# Button_Board_RevA.net
KiCad netlist of a schematic drawn in EAGLE
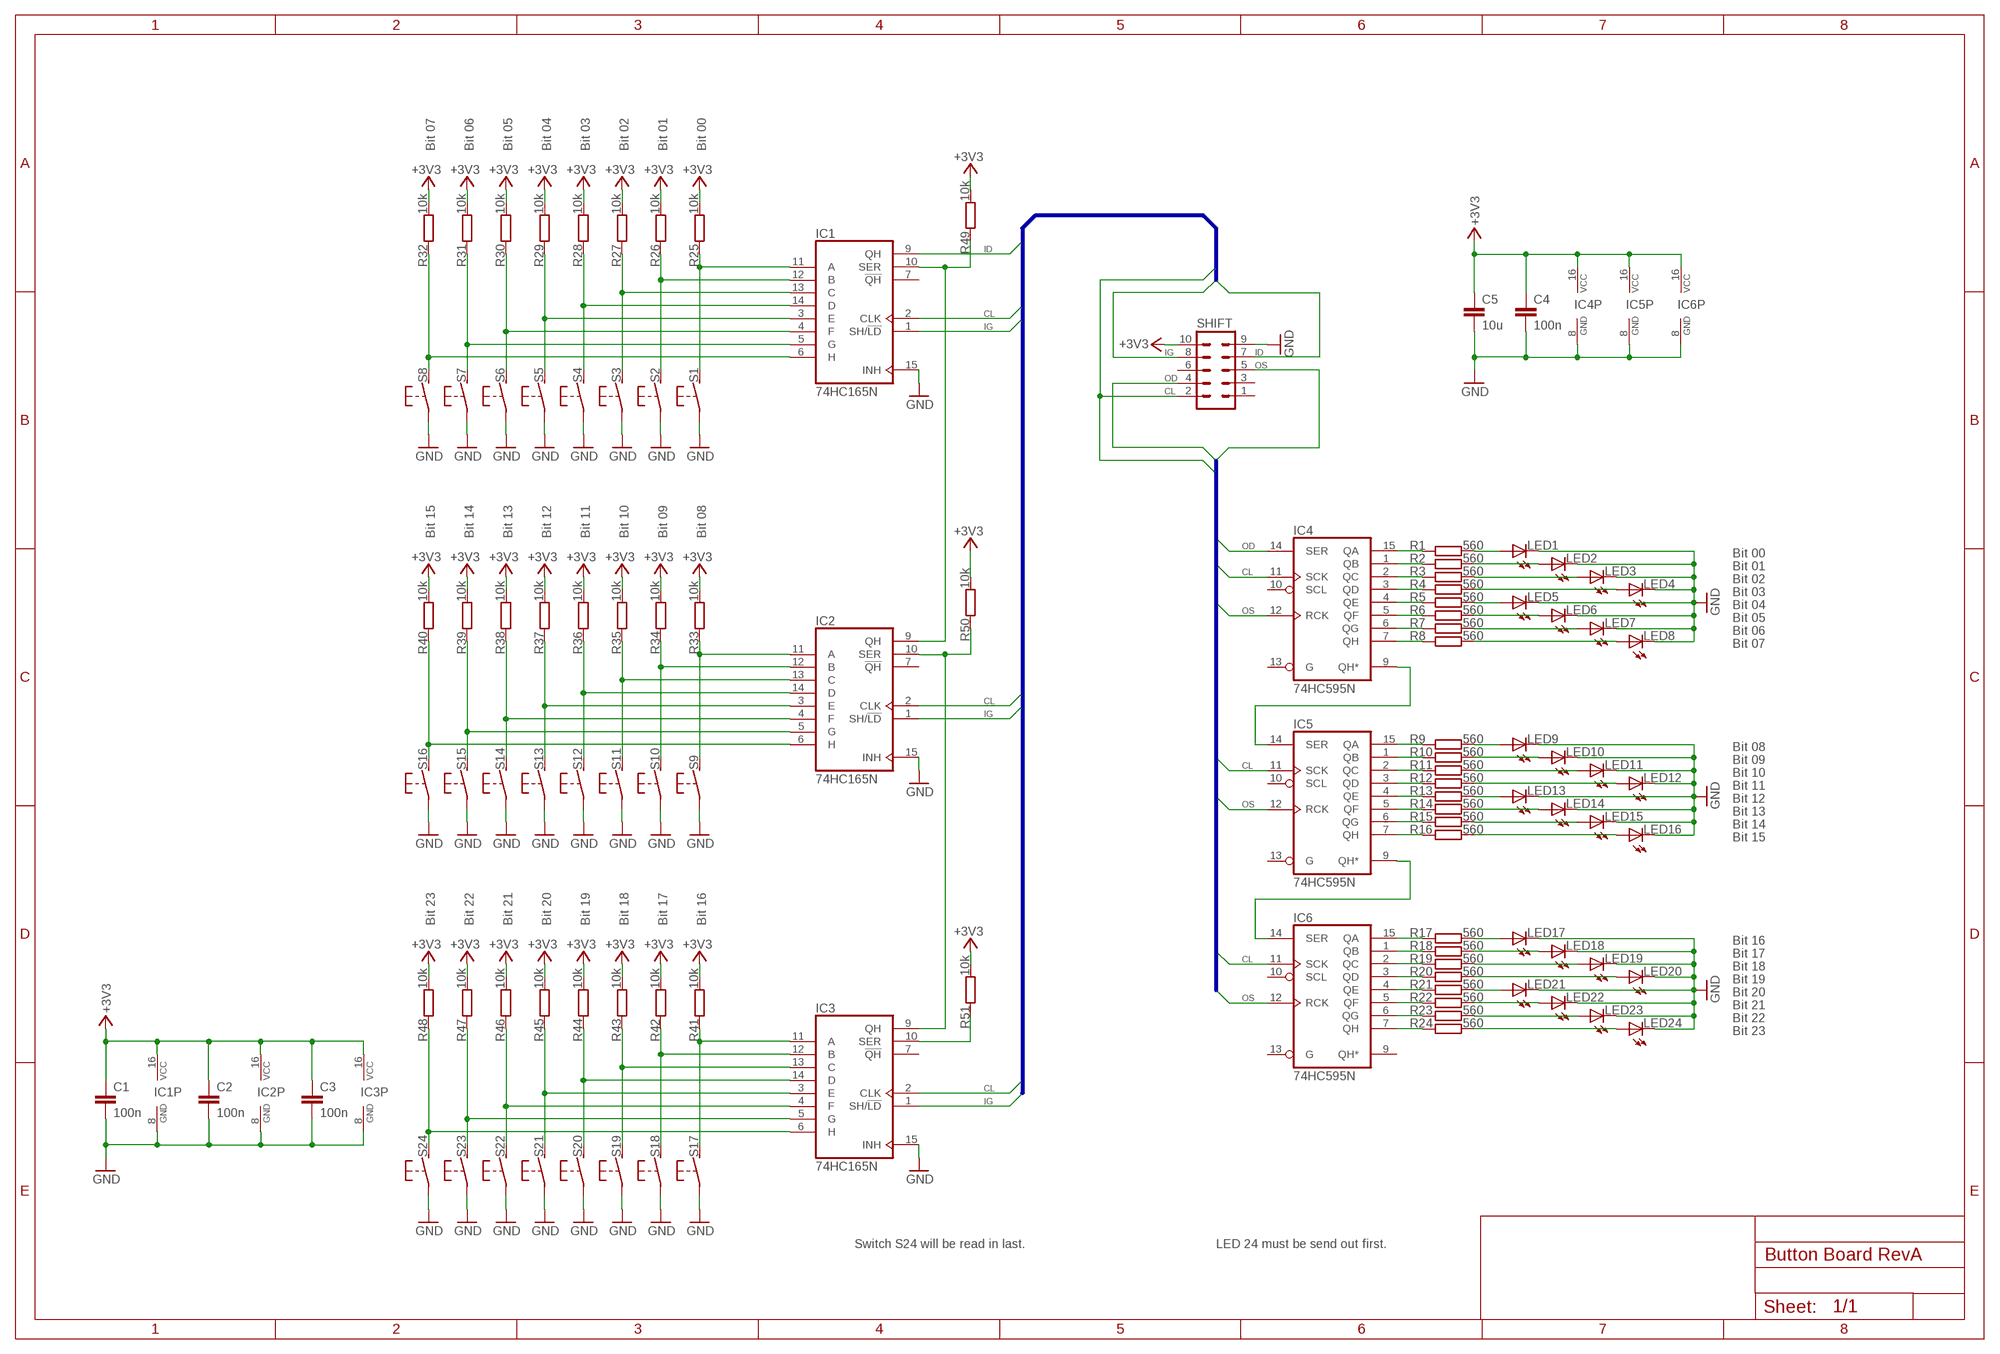
[diagram p0: schematic, sheet 1]

(export (version "E")
  (design (tool "Eeschema 10.0.6"))
  (components
    (comp (ref "C1")
      (value "100n")
      (footprint "eagle-import:C025-025X050")
      (libsource (lib "eagle-import") (part "C-EU025-025X050"))
    )
    (comp (ref "C2")
      (value "100n")
      (footprint "eagle-import:C025-025X050")
      (libsource (lib "eagle-import") (part "C-EU025-025X050"))
    )
    (comp (ref "C3")
      (value "100n")
      (footprint "eagle-import:C025-025X050")
      (libsource (lib "eagle-import") (part "C-EU025-025X050"))
    )
    (comp (ref "C4")
      (value "100n")
      (footprint "eagle-import:C025-025X050")
      (libsource (lib "eagle-import") (part "C-EU025-025X050"))
    )
    (comp (ref "C5")
      (value "10u")
      (footprint "eagle-import:C025-025X050")
      (libsource (lib "eagle-import") (part "C-EU025-025X050"))
    )
    (comp (ref "IC1")
      (value "74HC165N")
      (footprint "eagle-import:DIL16")
      (libsource (lib "eagle-import") (part "74165NHC"))
    )
    (comp (ref "IC2")
      (value "74HC165N")
      (footprint "eagle-import:DIL16")
      (libsource (lib "eagle-import") (part "74165NHC"))
    )
    (comp (ref "IC3")
      (value "74HC165N")
      (footprint "eagle-import:DIL16")
      (libsource (lib "eagle-import") (part "74165NHC"))
    )
    (comp (ref "IC4")
      (value "74HC595N")
      (footprint "eagle-import:DIL16")
      (libsource (lib "eagle-import") (part "74595NHC"))
    )
    (comp (ref "IC5")
      (value "74HC595N")
      (footprint "eagle-import:DIL16")
      (libsource (lib "eagle-import") (part "74595NHC"))
    )
    (comp (ref "IC6")
      (value "74HC595N")
      (footprint "eagle-import:DIL16")
      (libsource (lib "eagle-import") (part "74595NHC"))
    )
    (comp (ref "LED1")
      (value "LED3MM")
      (footprint "eagle-import:LED3MM")
      (libsource (lib "eagle-import") (part "LED3MM"))
    )
    (comp (ref "LED2")
      (value "LED3MM")
      (footprint "eagle-import:LED3MM")
      (libsource (lib "eagle-import") (part "LED3MM"))
    )
    (comp (ref "LED3")
      (value "LED3MM")
      (footprint "eagle-import:LED3MM")
      (libsource (lib "eagle-import") (part "LED3MM"))
    )
    (comp (ref "LED4")
      (value "LED3MM")
      (footprint "eagle-import:LED3MM")
      (libsource (lib "eagle-import") (part "LED3MM"))
    )
    (comp (ref "LED5")
      (value "LED3MM")
      (footprint "eagle-import:LED3MM")
      (libsource (lib "eagle-import") (part "LED3MM"))
    )
    (comp (ref "LED6")
      (value "LED3MM")
      (footprint "eagle-import:LED3MM")
      (libsource (lib "eagle-import") (part "LED3MM"))
    )
    (comp (ref "LED7")
      (value "LED3MM")
      (footprint "eagle-import:LED3MM")
      (libsource (lib "eagle-import") (part "LED3MM"))
    )
    (comp (ref "LED8")
      (value "LED3MM")
      (footprint "eagle-import:LED3MM")
      (libsource (lib "eagle-import") (part "LED3MM"))
    )
    (comp (ref "LED9")
      (value "LED3MM")
      (footprint "eagle-import:LED3MM")
      (libsource (lib "eagle-import") (part "LED3MM"))
    )
    (comp (ref "LED10")
      (value "LED3MM")
      (footprint "eagle-import:LED3MM")
      (libsource (lib "eagle-import") (part "LED3MM"))
    )
    (comp (ref "LED11")
      (value "LED3MM")
      (footprint "eagle-import:LED3MM")
      (libsource (lib "eagle-import") (part "LED3MM"))
    )
    (comp (ref "LED12")
      (value "LED3MM")
      (footprint "eagle-import:LED3MM")
      (libsource (lib "eagle-import") (part "LED3MM"))
    )
    (comp (ref "LED13")
      (value "LED3MM")
      (footprint "eagle-import:LED3MM")
      (libsource (lib "eagle-import") (part "LED3MM"))
    )
    (comp (ref "LED14")
      (value "LED3MM")
      (footprint "eagle-import:LED3MM")
      (libsource (lib "eagle-import") (part "LED3MM"))
    )
    (comp (ref "LED15")
      (value "LED3MM")
      (footprint "eagle-import:LED3MM")
      (libsource (lib "eagle-import") (part "LED3MM"))
    )
    (comp (ref "LED16")
      (value "LED3MM")
      (footprint "eagle-import:LED3MM")
      (libsource (lib "eagle-import") (part "LED3MM"))
    )
    (comp (ref "LED17")
      (value "LED3MM")
      (footprint "eagle-import:LED3MM")
      (libsource (lib "eagle-import") (part "LED3MM"))
    )
    (comp (ref "LED18")
      (value "LED3MM")
      (footprint "eagle-import:LED3MM")
      (libsource (lib "eagle-import") (part "LED3MM"))
    )
    (comp (ref "LED19")
      (value "LED3MM")
      (footprint "eagle-import:LED3MM")
      (libsource (lib "eagle-import") (part "LED3MM"))
    )
    (comp (ref "LED20")
      (value "LED3MM")
      (footprint "eagle-import:LED3MM")
      (libsource (lib "eagle-import") (part "LED3MM"))
    )
    (comp (ref "LED21")
      (value "LED3MM")
      (footprint "eagle-import:LED3MM")
      (libsource (lib "eagle-import") (part "LED3MM"))
    )
    (comp (ref "LED22")
      (value "LED3MM")
      (footprint "eagle-import:LED3MM")
      (libsource (lib "eagle-import") (part "LED3MM"))
    )
    (comp (ref "LED23")
      (value "LED3MM")
      (footprint "eagle-import:LED3MM")
      (libsource (lib "eagle-import") (part "LED3MM"))
    )
    (comp (ref "LED24")
      (value "LED3MM")
      (footprint "eagle-import:LED3MM")
      (libsource (lib "eagle-import") (part "LED3MM"))
    )
    (comp (ref "R1")
      (value "560")
      (footprint "eagle-import:0204_5")
      (libsource (lib "eagle-import") (part "R-EU_0204/5"))
    )
    (comp (ref "R2")
      (value "560")
      (footprint "eagle-import:0204_5")
      (libsource (lib "eagle-import") (part "R-EU_0204/5"))
    )
    (comp (ref "R3")
      (value "560")
      (footprint "eagle-import:0204_5")
      (libsource (lib "eagle-import") (part "R-EU_0204/5"))
    )
    (comp (ref "R4")
      (value "560")
      (footprint "eagle-import:0204_5")
      (libsource (lib "eagle-import") (part "R-EU_0204/5"))
    )
    (comp (ref "R5")
      (value "560")
      (footprint "eagle-import:0204_5")
      (libsource (lib "eagle-import") (part "R-EU_0204/5"))
    )
    (comp (ref "R6")
      (value "560")
      (footprint "eagle-import:0204_5")
      (libsource (lib "eagle-import") (part "R-EU_0204/5"))
    )
    (comp (ref "R7")
      (value "560")
      (footprint "eagle-import:0204_5")
      (libsource (lib "eagle-import") (part "R-EU_0204/5"))
    )
    (comp (ref "R8")
      (value "560")
      (footprint "eagle-import:0204_5")
      (libsource (lib "eagle-import") (part "R-EU_0204/5"))
    )
    (comp (ref "R9")
      (value "560")
      (footprint "eagle-import:0204_5")
      (libsource (lib "eagle-import") (part "R-EU_0204/5"))
    )
    (comp (ref "R10")
      (value "560")
      (footprint "eagle-import:0204_5")
      (libsource (lib "eagle-import") (part "R-EU_0204/5"))
    )
    (comp (ref "R11")
      (value "560")
      (footprint "eagle-import:0204_5")
      (libsource (lib "eagle-import") (part "R-EU_0204/5"))
    )
    (comp (ref "R12")
      (value "560")
      (footprint "eagle-import:0204_5")
      (libsource (lib "eagle-import") (part "R-EU_0204/5"))
    )
    (comp (ref "R13")
      (value "560")
      (footprint "eagle-import:0204_5")
      (libsource (lib "eagle-import") (part "R-EU_0204/5"))
    )
    (comp (ref "R14")
      (value "560")
      (footprint "eagle-import:0204_5")
      (libsource (lib "eagle-import") (part "R-EU_0204/5"))
    )
    (comp (ref "R15")
      (value "560")
      (footprint "eagle-import:0204_5")
      (libsource (lib "eagle-import") (part "R-EU_0204/5"))
    )
    (comp (ref "R16")
      (value "560")
      (footprint "eagle-import:0204_5")
      (libsource (lib "eagle-import") (part "R-EU_0204/5"))
    )
    (comp (ref "R17")
      (value "560")
      (footprint "eagle-import:0204_5")
      (libsource (lib "eagle-import") (part "R-EU_0204/5"))
    )
    (comp (ref "R18")
      (value "560")
      (footprint "eagle-import:0204_5")
      (libsource (lib "eagle-import") (part "R-EU_0204/5"))
    )
    (comp (ref "R19")
      (value "560")
      (footprint "eagle-import:0204_5")
      (libsource (lib "eagle-import") (part "R-EU_0204/5"))
    )
    (comp (ref "R20")
      (value "560")
      (footprint "eagle-import:0204_5")
      (libsource (lib "eagle-import") (part "R-EU_0204/5"))
    )
    (comp (ref "R21")
      (value "560")
      (footprint "eagle-import:0204_5")
      (libsource (lib "eagle-import") (part "R-EU_0204/5"))
    )
    (comp (ref "R22")
      (value "560")
      (footprint "eagle-import:0204_5")
      (libsource (lib "eagle-import") (part "R-EU_0204/5"))
    )
    (comp (ref "R23")
      (value "560")
      (footprint "eagle-import:0204_5")
      (libsource (lib "eagle-import") (part "R-EU_0204/5"))
    )
    (comp (ref "R24")
      (value "560")
      (footprint "eagle-import:0204_5")
      (libsource (lib "eagle-import") (part "R-EU_0204/5"))
    )
    (comp (ref "R25")
      (value "10k")
      (footprint "eagle-import:0204_5")
      (libsource (lib "eagle-import") (part "R-EU_0204/5"))
    )
    (comp (ref "R26")
      (value "10k")
      (footprint "eagle-import:0204_5")
      (libsource (lib "eagle-import") (part "R-EU_0204/5"))
    )
    (comp (ref "R27")
      (value "10k")
      (footprint "eagle-import:0204_5")
      (libsource (lib "eagle-import") (part "R-EU_0204/5"))
    )
    (comp (ref "R28")
      (value "10k")
      (footprint "eagle-import:0204_5")
      (libsource (lib "eagle-import") (part "R-EU_0204/5"))
    )
    (comp (ref "R29")
      (value "10k")
      (footprint "eagle-import:0204_5")
      (libsource (lib "eagle-import") (part "R-EU_0204/5"))
    )
    (comp (ref "R30")
      (value "10k")
      (footprint "eagle-import:0204_5")
      (libsource (lib "eagle-import") (part "R-EU_0204/5"))
    )
    (comp (ref "R31")
      (value "10k")
      (footprint "eagle-import:0204_5")
      (libsource (lib "eagle-import") (part "R-EU_0204/5"))
    )
    (comp (ref "R32")
      (value "10k")
      (footprint "eagle-import:0204_5")
      (libsource (lib "eagle-import") (part "R-EU_0204/5"))
    )
    (comp (ref "R33")
      (value "10k")
      (footprint "eagle-import:0204_5")
      (libsource (lib "eagle-import") (part "R-EU_0204/5"))
    )
    (comp (ref "R34")
      (value "10k")
      (footprint "eagle-import:0204_5")
      (libsource (lib "eagle-import") (part "R-EU_0204/5"))
    )
    (comp (ref "R35")
      (value "10k")
      (footprint "eagle-import:0204_5")
      (libsource (lib "eagle-import") (part "R-EU_0204/5"))
    )
    (comp (ref "R36")
      (value "10k")
      (footprint "eagle-import:0204_5")
      (libsource (lib "eagle-import") (part "R-EU_0204/5"))
    )
    (comp (ref "R37")
      (value "10k")
      (footprint "eagle-import:0204_5")
      (libsource (lib "eagle-import") (part "R-EU_0204/5"))
    )
    (comp (ref "R38")
      (value "10k")
      (footprint "eagle-import:0204_5")
      (libsource (lib "eagle-import") (part "R-EU_0204/5"))
    )
    (comp (ref "R39")
      (value "10k")
      (footprint "eagle-import:0204_5")
      (libsource (lib "eagle-import") (part "R-EU_0204/5"))
    )
    (comp (ref "R40")
      (value "10k")
      (footprint "eagle-import:0204_5")
      (libsource (lib "eagle-import") (part "R-EU_0204/5"))
    )
    (comp (ref "R41")
      (value "10k")
      (footprint "eagle-import:0204_5")
      (libsource (lib "eagle-import") (part "R-EU_0204/5"))
    )
    (comp (ref "R42")
      (value "10k")
      (footprint "eagle-import:0204_5")
      (libsource (lib "eagle-import") (part "R-EU_0204/5"))
    )
    (comp (ref "R43")
      (value "10k")
      (footprint "eagle-import:0204_5")
      (libsource (lib "eagle-import") (part "R-EU_0204/5"))
    )
    (comp (ref "R44")
      (value "10k")
      (footprint "eagle-import:0204_5")
      (libsource (lib "eagle-import") (part "R-EU_0204/5"))
    )
    (comp (ref "R45")
      (value "10k")
      (footprint "eagle-import:0204_5")
      (libsource (lib "eagle-import") (part "R-EU_0204/5"))
    )
    (comp (ref "R46")
      (value "10k")
      (footprint "eagle-import:0204_5")
      (libsource (lib "eagle-import") (part "R-EU_0204/5"))
    )
    (comp (ref "R47")
      (value "10k")
      (footprint "eagle-import:0204_5")
      (libsource (lib "eagle-import") (part "R-EU_0204/5"))
    )
    (comp (ref "R48")
      (value "10k")
      (footprint "eagle-import:0204_5")
      (libsource (lib "eagle-import") (part "R-EU_0204/5"))
    )
    (comp (ref "R49")
      (value "10k")
      (footprint "eagle-import:0204_5")
      (libsource (lib "eagle-import") (part "R-EU_0204/5"))
    )
    (comp (ref "R50")
      (value "10k")
      (footprint "eagle-import:0204_5")
      (libsource (lib "eagle-import") (part "R-EU_0204/5"))
    )
    (comp (ref "R51")
      (value "10k")
      (footprint "eagle-import:0204_5")
      (libsource (lib "eagle-import") (part "R-EU_0204/5"))
    )
    (comp (ref "S1")
      (value "31-XX")
      (footprint "eagle-import:B3F-31XX")
      (fields (field (name "MPN") "B3F-3100"))
      (libsource (lib "eagle-import") (part "31-XX"))
    )
    (comp (ref "S2")
      (value "31-XX")
      (footprint "eagle-import:B3F-31XX")
      (fields (field (name "MPN") "B3F-3100"))
      (libsource (lib "eagle-import") (part "31-XX"))
    )
    (comp (ref "S3")
      (value "31-XX")
      (footprint "eagle-import:B3F-31XX")
      (fields (field (name "MPN") "B3F-3100"))
      (libsource (lib "eagle-import") (part "31-XX"))
    )
    (comp (ref "S4")
      (value "31-XX")
      (footprint "eagle-import:B3F-31XX")
      (fields (field (name "MPN") "B3F-3100"))
      (libsource (lib "eagle-import") (part "31-XX"))
    )
    (comp (ref "S5")
      (value "31-XX")
      (footprint "eagle-import:B3F-31XX")
      (fields (field (name "MPN") "B3F-3100"))
      (libsource (lib "eagle-import") (part "31-XX"))
    )
    (comp (ref "S6")
      (value "31-XX")
      (footprint "eagle-import:B3F-31XX")
      (fields (field (name "MPN") "B3F-3100"))
      (libsource (lib "eagle-import") (part "31-XX"))
    )
    (comp (ref "S7")
      (value "31-XX")
      (footprint "eagle-import:B3F-31XX")
      (fields (field (name "MPN") "B3F-3100"))
      (libsource (lib "eagle-import") (part "31-XX"))
    )
    (comp (ref "S8")
      (value "31-XX")
      (footprint "eagle-import:B3F-31XX")
      (fields (field (name "MPN") "B3F-3100"))
      (libsource (lib "eagle-import") (part "31-XX"))
    )
    (comp (ref "S9")
      (value "31-XX")
      (footprint "eagle-import:B3F-31XX")
      (fields (field (name "MPN") "B3F-3100"))
      (libsource (lib "eagle-import") (part "31-XX"))
    )
    (comp (ref "S10")
      (value "31-XX")
      (footprint "eagle-import:B3F-31XX")
      (fields (field (name "MPN") "B3F-3100"))
      (libsource (lib "eagle-import") (part "31-XX"))
    )
    (comp (ref "S11")
      (value "31-XX")
      (footprint "eagle-import:B3F-31XX")
      (fields (field (name "MPN") "B3F-3100"))
      (libsource (lib "eagle-import") (part "31-XX"))
    )
    (comp (ref "S12")
      (value "31-XX")
      (footprint "eagle-import:B3F-31XX")
      (fields (field (name "MPN") "B3F-3100"))
      (libsource (lib "eagle-import") (part "31-XX"))
    )
    (comp (ref "S13")
      (value "31-XX")
      (footprint "eagle-import:B3F-31XX")
      (fields (field (name "MPN") "B3F-3100"))
      (libsource (lib "eagle-import") (part "31-XX"))
    )
    (comp (ref "S14")
      (value "31-XX")
      (footprint "eagle-import:B3F-31XX")
      (fields (field (name "MPN") "B3F-3100"))
      (libsource (lib "eagle-import") (part "31-XX"))
    )
    (comp (ref "S15")
      (value "31-XX")
      (footprint "eagle-import:B3F-31XX")
      (fields (field (name "MPN") "B3F-3100"))
      (libsource (lib "eagle-import") (part "31-XX"))
    )
    (comp (ref "S16")
      (value "31-XX")
      (footprint "eagle-import:B3F-31XX")
      (fields (field (name "MPN") "B3F-3100"))
      (libsource (lib "eagle-import") (part "31-XX"))
    )
    (comp (ref "S17")
      (value "31-XX")
      (footprint "eagle-import:B3F-31XX")
      (fields (field (name "MPN") "B3F-3100"))
      (libsource (lib "eagle-import") (part "31-XX"))
    )
    (comp (ref "S18")
      (value "31-XX")
      (footprint "eagle-import:B3F-31XX")
      (fields (field (name "MPN") "B3F-3100"))
      (libsource (lib "eagle-import") (part "31-XX"))
    )
    (comp (ref "S19")
      (value "31-XX")
      (footprint "eagle-import:B3F-31XX")
      (fields (field (name "MPN") "B3F-3100"))
      (libsource (lib "eagle-import") (part "31-XX"))
    )
    (comp (ref "S20")
      (value "31-XX")
      (footprint "eagle-import:B3F-31XX")
      (fields (field (name "MPN") "B3F-3100"))
      (libsource (lib "eagle-import") (part "31-XX"))
    )
    (comp (ref "S21")
      (value "31-XX")
      (footprint "eagle-import:B3F-31XX")
      (fields (field (name "MPN") "B3F-3100"))
      (libsource (lib "eagle-import") (part "31-XX"))
    )
    (comp (ref "S22")
      (value "31-XX")
      (footprint "eagle-import:B3F-31XX")
      (fields (field (name "MPN") "B3F-3100"))
      (libsource (lib "eagle-import") (part "31-XX"))
    )
    (comp (ref "S23")
      (value "31-XX")
      (footprint "eagle-import:B3F-31XX")
      (fields (field (name "MPN") "B3F-3100"))
      (libsource (lib "eagle-import") (part "31-XX"))
    )
    (comp (ref "S24")
      (value "31-XX")
      (footprint "eagle-import:B3F-31XX")
      (fields (field (name "MPN") "B3F-3100"))
      (libsource (lib "eagle-import") (part "31-XX"))
    )
    (comp (ref "SHIFT")
      (value "ML10")
      (footprint "eagle-import:ML10")
      (libsource (lib "eagle-import") (part "ML10"))
    )
  )
  (nets
    (net (code "1") (name "+3V3") (class "Default")
      (node (ref "C1") (pin "1") (pinfunction "1_1") (pintype "passive"))
      (node (ref "C2") (pin "1") (pinfunction "1_1") (pintype "passive"))
      (node (ref "C3") (pin "1") (pinfunction "1_1") (pintype "passive"))
      (node (ref "C4") (pin "1") (pinfunction "1_1") (pintype "passive"))
      (node (ref "C5") (pin "1") (pinfunction "1_1") (pintype "passive"))
      (node (ref "IC1") (pin "16") (pinfunction "VCC_16") (pintype "power_in"))
      (node (ref "IC2") (pin "16") (pinfunction "VCC_16") (pintype "power_in"))
      (node (ref "IC3") (pin "16") (pinfunction "VCC_16") (pintype "power_in"))
      (node (ref "IC4") (pin "16") (pinfunction "VCC_16") (pintype "power_in"))
      (node (ref "IC5") (pin "16") (pinfunction "VCC_16") (pintype "power_in"))
      (node (ref "IC6") (pin "16") (pinfunction "VCC_16") (pintype "power_in"))
      (node (ref "R25") (pin "2") (pinfunction "2_2") (pintype "passive"))
      (node (ref "R26") (pin "2") (pinfunction "2_2") (pintype "passive"))
      (node (ref "R27") (pin "2") (pinfunction "2_2") (pintype "passive"))
      (node (ref "R28") (pin "2") (pinfunction "2_2") (pintype "passive"))
      (node (ref "R29") (pin "2") (pinfunction "2_2") (pintype "passive"))
      (node (ref "R30") (pin "2") (pinfunction "2_2") (pintype "passive"))
      (node (ref "R31") (pin "2") (pinfunction "2_2") (pintype "passive"))
      (node (ref "R32") (pin "2") (pinfunction "2_2") (pintype "passive"))
      (node (ref "R33") (pin "2") (pinfunction "2_2") (pintype "passive"))
      (node (ref "R34") (pin "2") (pinfunction "2_2") (pintype "passive"))
      (node (ref "R35") (pin "2") (pinfunction "2_2") (pintype "passive"))
      (node (ref "R36") (pin "2") (pinfunction "2_2") (pintype "passive"))
      (node (ref "R37") (pin "2") (pinfunction "2_2") (pintype "passive"))
      (node (ref "R38") (pin "2") (pinfunction "2_2") (pintype "passive"))
      (node (ref "R39") (pin "2") (pinfunction "2_2") (pintype "passive"))
      (node (ref "R40") (pin "2") (pinfunction "2_2") (pintype "passive"))
      (node (ref "R41") (pin "2") (pinfunction "2_2") (pintype "passive"))
      (node (ref "R42") (pin "2") (pinfunction "2_2") (pintype "passive"))
      (node (ref "R43") (pin "2") (pinfunction "2_2") (pintype "passive"))
      (node (ref "R44") (pin "2") (pinfunction "2_2") (pintype "passive"))
      (node (ref "R45") (pin "2") (pinfunction "2_2") (pintype "passive"))
      (node (ref "R46") (pin "2") (pinfunction "2_2") (pintype "passive"))
      (node (ref "R47") (pin "2") (pinfunction "2_2") (pintype "passive"))
      (node (ref "R48") (pin "2") (pinfunction "2_2") (pintype "passive"))
      (node (ref "R49") (pin "2") (pinfunction "2_2") (pintype "passive"))
      (node (ref "R50") (pin "2") (pinfunction "2_2") (pintype "passive"))
      (node (ref "R51") (pin "2") (pinfunction "2_2") (pintype "passive"))
      (node (ref "SHIFT") (pin "10") (pinfunction "10_10") (pintype "passive"))
    )
    (net (code "2") (name "/CL") (class "Default")
      (node (ref "IC1") (pin "2") (pinfunction "CLK_2") (pintype "input"))
      (node (ref "IC2") (pin "2") (pinfunction "CLK_2") (pintype "input"))
      (node (ref "IC3") (pin "2") (pinfunction "CLK_2") (pintype "input"))
      (node (ref "IC4") (pin "11") (pinfunction "SCK_11") (pintype "input"))
      (node (ref "IC5") (pin "11") (pinfunction "SCK_11") (pintype "input"))
      (node (ref "IC6") (pin "11") (pinfunction "SCK_11") (pintype "input"))
      (node (ref "SHIFT") (pin "2") (pinfunction "2_2") (pintype "passive"))
    )
    (net (code "3") (name "/ID") (class "Default")
      (node (ref "IC1") (pin "9") (pinfunction "QH_9") (pintype "output"))
      (node (ref "SHIFT") (pin "7") (pinfunction "7_7") (pintype "passive"))
    )
    (net (code "4") (name "/IG") (class "Default")
      (node (ref "IC1") (pin "1") (pinfunction "SH/~{LD}_1") (pintype "input"))
      (node (ref "IC2") (pin "1") (pinfunction "SH/~{LD}_1") (pintype "input"))
      (node (ref "IC3") (pin "1") (pinfunction "SH/~{LD}_1") (pintype "input"))
      (node (ref "SHIFT") (pin "8") (pinfunction "8_8") (pintype "passive"))
    )
    (net (code "5") (name "/OD") (class "Default")
      (node (ref "IC4") (pin "14") (pinfunction "SER_14") (pintype "input"))
      (node (ref "SHIFT") (pin "4") (pinfunction "4_4") (pintype "passive"))
    )
    (net (code "6") (name "/OS") (class "Default")
      (node (ref "IC4") (pin "12") (pinfunction "RCK_12") (pintype "input"))
      (node (ref "IC5") (pin "12") (pinfunction "RCK_12") (pintype "input"))
      (node (ref "IC6") (pin "12") (pinfunction "RCK_12") (pintype "input"))
      (node (ref "SHIFT") (pin "5") (pinfunction "5_5") (pintype "passive"))
    )
    (net (code "7") (name "GND") (class "Default")
      (node (ref "C1") (pin "2") (pinfunction "2_2") (pintype "passive"))
      (node (ref "C2") (pin "2") (pinfunction "2_2") (pintype "passive"))
      (node (ref "C3") (pin "2") (pinfunction "2_2") (pintype "passive"))
      (node (ref "C4") (pin "2") (pinfunction "2_2") (pintype "passive"))
      (node (ref "C5") (pin "2") (pinfunction "2_2") (pintype "passive"))
      (node (ref "IC1") (pin "15") (pinfunction "INH_15") (pintype "input"))
      (node (ref "IC1") (pin "8") (pinfunction "GND_8") (pintype "power_in"))
      (node (ref "IC2") (pin "15") (pinfunction "INH_15") (pintype "input"))
      (node (ref "IC2") (pin "8") (pinfunction "GND_8") (pintype "power_in"))
      (node (ref "IC3") (pin "15") (pinfunction "INH_15") (pintype "input"))
      (node (ref "IC3") (pin "8") (pinfunction "GND_8") (pintype "power_in"))
      (node (ref "IC4") (pin "8") (pinfunction "GND_8") (pintype "power_in"))
      (node (ref "IC5") (pin "8") (pinfunction "GND_8") (pintype "power_in"))
      (node (ref "IC6") (pin "8") (pinfunction "GND_8") (pintype "power_in"))
      (node (ref "LED1") (pin "K") (pinfunction "C_K") (pintype "passive"))
      (node (ref "LED10") (pin "K") (pinfunction "C_K") (pintype "passive"))
      (node (ref "LED11") (pin "K") (pinfunction "C_K") (pintype "passive"))
      (node (ref "LED12") (pin "K") (pinfunction "C_K") (pintype "passive"))
      (node (ref "LED13") (pin "K") (pinfunction "C_K") (pintype "passive"))
      (node (ref "LED14") (pin "K") (pinfunction "C_K") (pintype "passive"))
      (node (ref "LED15") (pin "K") (pinfunction "C_K") (pintype "passive"))
      (node (ref "LED16") (pin "K") (pinfunction "C_K") (pintype "passive"))
      (node (ref "LED17") (pin "K") (pinfunction "C_K") (pintype "passive"))
      (node (ref "LED18") (pin "K") (pinfunction "C_K") (pintype "passive"))
      (node (ref "LED19") (pin "K") (pinfunction "C_K") (pintype "passive"))
      (node (ref "LED2") (pin "K") (pinfunction "C_K") (pintype "passive"))
      (node (ref "LED20") (pin "K") (pinfunction "C_K") (pintype "passive"))
      (node (ref "LED21") (pin "K") (pinfunction "C_K") (pintype "passive"))
      (node (ref "LED22") (pin "K") (pinfunction "C_K") (pintype "passive"))
      (node (ref "LED23") (pin "K") (pinfunction "C_K") (pintype "passive"))
      (node (ref "LED24") (pin "K") (pinfunction "C_K") (pintype "passive"))
      (node (ref "LED3") (pin "K") (pinfunction "C_K") (pintype "passive"))
      (node (ref "LED4") (pin "K") (pinfunction "C_K") (pintype "passive"))
      (node (ref "LED5") (pin "K") (pinfunction "C_K") (pintype "passive"))
      (node (ref "LED6") (pin "K") (pinfunction "C_K") (pintype "passive"))
      (node (ref "LED7") (pin "K") (pinfunction "C_K") (pintype "passive"))
      (node (ref "LED8") (pin "K") (pinfunction "C_K") (pintype "passive"))
      (node (ref "LED9") (pin "K") (pinfunction "C_K") (pintype "passive"))
      (node (ref "S1") (pin "1") (pinfunction "P_1") (pintype "passive"))
      (node (ref "S10") (pin "1") (pinfunction "P_1") (pintype "passive"))
      (node (ref "S11") (pin "1") (pinfunction "P_1") (pintype "passive"))
      (node (ref "S12") (pin "1") (pinfunction "P_1") (pintype "passive"))
      (node (ref "S13") (pin "1") (pinfunction "P_1") (pintype "passive"))
      (node (ref "S14") (pin "1") (pinfunction "P_1") (pintype "passive"))
      (node (ref "S15") (pin "1") (pinfunction "P_1") (pintype "passive"))
      (node (ref "S16") (pin "1") (pinfunction "P_1") (pintype "passive"))
      (node (ref "S17") (pin "1") (pinfunction "P_1") (pintype "passive"))
      (node (ref "S18") (pin "1") (pinfunction "P_1") (pintype "passive"))
      (node (ref "S19") (pin "1") (pinfunction "P_1") (pintype "passive"))
      (node (ref "S2") (pin "1") (pinfunction "P_1") (pintype "passive"))
      (node (ref "S20") (pin "1") (pinfunction "P_1") (pintype "passive"))
      (node (ref "S21") (pin "1") (pinfunction "P_1") (pintype "passive"))
      (node (ref "S22") (pin "1") (pinfunction "P_1") (pintype "passive"))
      (node (ref "S23") (pin "1") (pinfunction "P_1") (pintype "passive"))
      (node (ref "S24") (pin "1") (pinfunction "P_1") (pintype "passive"))
      (node (ref "S3") (pin "1") (pinfunction "P_1") (pintype "passive"))
      (node (ref "S4") (pin "1") (pinfunction "P_1") (pintype "passive"))
      (node (ref "S5") (pin "1") (pinfunction "P_1") (pintype "passive"))
      (node (ref "S6") (pin "1") (pinfunction "P_1") (pintype "passive"))
      (node (ref "S7") (pin "1") (pinfunction "P_1") (pintype "passive"))
      (node (ref "S8") (pin "1") (pinfunction "P_1") (pintype "passive"))
      (node (ref "S9") (pin "1") (pinfunction "P_1") (pintype "passive"))
      (node (ref "SHIFT") (pin "9") (pinfunction "9_9") (pintype "passive"))
    )
    (net (code "8") (name "Net-(IC1A-A)") (class "Default")
      (node (ref "IC1") (pin "11") (pinfunction "A_11") (pintype "input"))
      (node (ref "R25") (pin "1") (pinfunction "1_1") (pintype "passive"))
      (node (ref "S1") (pin "2") (pinfunction "S_2") (pintype "passive"))
    )
    (net (code "9") (name "Net-(IC1A-B)") (class "Default")
      (node (ref "IC1") (pin "12") (pinfunction "B_12") (pintype "input"))
      (node (ref "R26") (pin "1") (pinfunction "1_1") (pintype "passive"))
      (node (ref "S2") (pin "2") (pinfunction "S_2") (pintype "passive"))
    )
    (net (code "10") (name "Net-(IC1A-C)") (class "Default")
      (node (ref "IC1") (pin "13") (pinfunction "C_13") (pintype "input"))
      (node (ref "R27") (pin "1") (pinfunction "1_1") (pintype "passive"))
      (node (ref "S3") (pin "2") (pinfunction "S_2") (pintype "passive"))
    )
    (net (code "11") (name "Net-(IC1A-D)") (class "Default")
      (node (ref "IC1") (pin "14") (pinfunction "D_14") (pintype "input"))
      (node (ref "R28") (pin "1") (pinfunction "1_1") (pintype "passive"))
      (node (ref "S4") (pin "2") (pinfunction "S_2") (pintype "passive"))
    )
    (net (code "12") (name "Net-(IC1A-E)") (class "Default")
      (node (ref "IC1") (pin "3") (pinfunction "E_3") (pintype "input"))
      (node (ref "R29") (pin "1") (pinfunction "1_1") (pintype "passive"))
      (node (ref "S5") (pin "2") (pinfunction "S_2") (pintype "passive"))
    )
    (net (code "13") (name "Net-(IC1A-F)") (class "Default")
      (node (ref "IC1") (pin "4") (pinfunction "F_4") (pintype "input"))
      (node (ref "R30") (pin "1") (pinfunction "1_1") (pintype "passive"))
      (node (ref "S6") (pin "2") (pinfunction "S_2") (pintype "passive"))
    )
    (net (code "14") (name "Net-(IC1A-G)") (class "Default")
      (node (ref "IC1") (pin "5") (pinfunction "G_5") (pintype "input"))
      (node (ref "R31") (pin "1") (pinfunction "1_1") (pintype "passive"))
      (node (ref "S7") (pin "2") (pinfunction "S_2") (pintype "passive"))
    )
    (net (code "15") (name "Net-(IC1A-H)") (class "Default")
      (node (ref "IC1") (pin "6") (pinfunction "H_6") (pintype "input"))
      (node (ref "R32") (pin "1") (pinfunction "1_1") (pintype "passive"))
      (node (ref "S8") (pin "2") (pinfunction "S_2") (pintype "passive"))
    )
    (net (code "16") (name "Net-(IC1A-SER)") (class "Default")
      (node (ref "IC1") (pin "10") (pinfunction "SER_10") (pintype "input"))
      (node (ref "IC2") (pin "9") (pinfunction "QH_9") (pintype "output"))
      (node (ref "R49") (pin "1") (pinfunction "1_1") (pintype "passive"))
    )
    (net (code "17") (name "Net-(IC2A-A)") (class "Default")
      (node (ref "IC2") (pin "11") (pinfunction "A_11") (pintype "input"))
      (node (ref "R33") (pin "1") (pinfunction "1_1") (pintype "passive"))
      (node (ref "S9") (pin "2") (pinfunction "S_2") (pintype "passive"))
    )
    (net (code "18") (name "Net-(IC2A-B)") (class "Default")
      (node (ref "IC2") (pin "12") (pinfunction "B_12") (pintype "input"))
      (node (ref "R34") (pin "1") (pinfunction "1_1") (pintype "passive"))
      (node (ref "S10") (pin "2") (pinfunction "S_2") (pintype "passive"))
    )
    (net (code "19") (name "Net-(IC2A-C)") (class "Default")
      (node (ref "IC2") (pin "13") (pinfunction "C_13") (pintype "input"))
      (node (ref "R35") (pin "1") (pinfunction "1_1") (pintype "passive"))
      (node (ref "S11") (pin "2") (pinfunction "S_2") (pintype "passive"))
    )
    (net (code "20") (name "Net-(IC2A-D)") (class "Default")
      (node (ref "IC2") (pin "14") (pinfunction "D_14") (pintype "input"))
      (node (ref "R36") (pin "1") (pinfunction "1_1") (pintype "passive"))
      (node (ref "S12") (pin "2") (pinfunction "S_2") (pintype "passive"))
    )
    (net (code "21") (name "Net-(IC2A-E)") (class "Default")
      (node (ref "IC2") (pin "3") (pinfunction "E_3") (pintype "input"))
      (node (ref "R37") (pin "1") (pinfunction "1_1") (pintype "passive"))
      (node (ref "S13") (pin "2") (pinfunction "S_2") (pintype "passive"))
    )
    (net (code "22") (name "Net-(IC2A-F)") (class "Default")
      (node (ref "IC2") (pin "4") (pinfunction "F_4") (pintype "input"))
      (node (ref "R38") (pin "1") (pinfunction "1_1") (pintype "passive"))
      (node (ref "S14") (pin "2") (pinfunction "S_2") (pintype "passive"))
    )
    (net (code "23") (name "Net-(IC2A-G)") (class "Default")
      (node (ref "IC2") (pin "5") (pinfunction "G_5") (pintype "input"))
      (node (ref "R39") (pin "1") (pinfunction "1_1") (pintype "passive"))
      (node (ref "S15") (pin "2") (pinfunction "S_2") (pintype "passive"))
    )
    (net (code "24") (name "Net-(IC2A-H)") (class "Default")
      (node (ref "IC2") (pin "6") (pinfunction "H_6") (pintype "input"))
      (node (ref "R40") (pin "1") (pinfunction "1_1") (pintype "passive"))
      (node (ref "S16") (pin "2") (pinfunction "S_2") (pintype "passive"))
    )
    (net (code "25") (name "Net-(IC2A-SER)") (class "Default")
      (node (ref "IC2") (pin "10") (pinfunction "SER_10") (pintype "input"))
      (node (ref "IC3") (pin "9") (pinfunction "QH_9") (pintype "output"))
      (node (ref "R50") (pin "1") (pinfunction "1_1") (pintype "passive"))
    )
    (net (code "26") (name "Net-(IC3A-A)") (class "Default")
      (node (ref "IC3") (pin "11") (pinfunction "A_11") (pintype "input"))
      (node (ref "R41") (pin "1") (pinfunction "1_1") (pintype "passive"))
      (node (ref "S17") (pin "2") (pinfunction "S_2") (pintype "passive"))
    )
    (net (code "27") (name "Net-(IC3A-B)") (class "Default")
      (node (ref "IC3") (pin "12") (pinfunction "B_12") (pintype "input"))
      (node (ref "R42") (pin "1") (pinfunction "1_1") (pintype "passive"))
      (node (ref "S18") (pin "2") (pinfunction "S_2") (pintype "passive"))
    )
    (net (code "28") (name "Net-(IC3A-C)") (class "Default")
      (node (ref "IC3") (pin "13") (pinfunction "C_13") (pintype "input"))
      (node (ref "R43") (pin "1") (pinfunction "1_1") (pintype "passive"))
      (node (ref "S19") (pin "2") (pinfunction "S_2") (pintype "passive"))
    )
    (net (code "29") (name "Net-(IC3A-D)") (class "Default")
      (node (ref "IC3") (pin "14") (pinfunction "D_14") (pintype "input"))
      (node (ref "R44") (pin "1") (pinfunction "1_1") (pintype "passive"))
      (node (ref "S20") (pin "2") (pinfunction "S_2") (pintype "passive"))
    )
    (net (code "30") (name "Net-(IC3A-E)") (class "Default")
      (node (ref "IC3") (pin "3") (pinfunction "E_3") (pintype "input"))
      (node (ref "R45") (pin "1") (pinfunction "1_1") (pintype "passive"))
      (node (ref "S21") (pin "2") (pinfunction "S_2") (pintype "passive"))
    )
    (net (code "31") (name "Net-(IC3A-F)") (class "Default")
      (node (ref "IC3") (pin "4") (pinfunction "F_4") (pintype "input"))
      (node (ref "R46") (pin "1") (pinfunction "1_1") (pintype "passive"))
      (node (ref "S22") (pin "2") (pinfunction "S_2") (pintype "passive"))
    )
    (net (code "32") (name "Net-(IC3A-G)") (class "Default")
      (node (ref "IC3") (pin "5") (pinfunction "G_5") (pintype "input"))
      (node (ref "R47") (pin "1") (pinfunction "1_1") (pintype "passive"))
      (node (ref "S23") (pin "2") (pinfunction "S_2") (pintype "passive"))
    )
    (net (code "33") (name "Net-(IC3A-H)") (class "Default")
      (node (ref "IC3") (pin "6") (pinfunction "H_6") (pintype "input"))
      (node (ref "R48") (pin "1") (pinfunction "1_1") (pintype "passive"))
      (node (ref "S24") (pin "2") (pinfunction "S_2") (pintype "passive"))
    )
    (net (code "34") (name "Net-(IC3A-SER)") (class "Default")
      (node (ref "IC3") (pin "10") (pinfunction "SER_10") (pintype "input"))
      (node (ref "R51") (pin "1") (pinfunction "1_1") (pintype "passive"))
    )
    (net (code "35") (name "Net-(IC4A-QA)") (class "Default")
      (node (ref "IC4") (pin "15") (pinfunction "QA_15") (pintype "tri_state"))
      (node (ref "R1") (pin "1") (pinfunction "1_1") (pintype "passive"))
    )
    (net (code "36") (name "Net-(IC4A-QB)") (class "Default")
      (node (ref "IC4") (pin "1") (pinfunction "QB_1") (pintype "tri_state"))
      (node (ref "R2") (pin "1") (pinfunction "1_1") (pintype "passive"))
    )
    (net (code "37") (name "Net-(IC4A-QC)") (class "Default")
      (node (ref "IC4") (pin "2") (pinfunction "QC_2") (pintype "tri_state"))
      (node (ref "R3") (pin "1") (pinfunction "1_1") (pintype "passive"))
    )
    (net (code "38") (name "Net-(IC4A-QD)") (class "Default")
      (node (ref "IC4") (pin "3") (pinfunction "QD_3") (pintype "tri_state"))
      (node (ref "R4") (pin "1") (pinfunction "1_1") (pintype "passive"))
    )
    (net (code "39") (name "Net-(IC4A-QE)") (class "Default")
      (node (ref "IC4") (pin "4") (pinfunction "QE_4") (pintype "tri_state"))
      (node (ref "R5") (pin "1") (pinfunction "1_1") (pintype "passive"))
    )
    (net (code "40") (name "Net-(IC4A-QF)") (class "Default")
      (node (ref "IC4") (pin "5") (pinfunction "QF_5") (pintype "tri_state"))
      (node (ref "R6") (pin "1") (pinfunction "1_1") (pintype "passive"))
    )
    (net (code "41") (name "Net-(IC4A-QG)") (class "Default")
      (node (ref "IC4") (pin "6") (pinfunction "QG_6") (pintype "tri_state"))
      (node (ref "R7") (pin "1") (pinfunction "1_1") (pintype "passive"))
    )
    (net (code "42") (name "Net-(IC4A-QH)") (class "Default")
      (node (ref "IC4") (pin "7") (pinfunction "QH_7") (pintype "tri_state"))
      (node (ref "R8") (pin "1") (pinfunction "1_1") (pintype "passive"))
    )
    (net (code "43") (name "Net-(IC4A-QH*)") (class "Default")
      (node (ref "IC4") (pin "9") (pinfunction "QH*_9") (pintype "tri_state"))
      (node (ref "IC5") (pin "14") (pinfunction "SER_14") (pintype "input"))
    )
    (net (code "44") (name "Net-(IC5A-QA)") (class "Default")
      (node (ref "IC5") (pin "15") (pinfunction "QA_15") (pintype "tri_state"))
      (node (ref "R9") (pin "1") (pinfunction "1_1") (pintype "passive"))
    )
    (net (code "45") (name "Net-(IC5A-QB)") (class "Default")
      (node (ref "IC5") (pin "1") (pinfunction "QB_1") (pintype "tri_state"))
      (node (ref "R10") (pin "1") (pinfunction "1_1") (pintype "passive"))
    )
    (net (code "46") (name "Net-(IC5A-QC)") (class "Default")
      (node (ref "IC5") (pin "2") (pinfunction "QC_2") (pintype "tri_state"))
      (node (ref "R11") (pin "1") (pinfunction "1_1") (pintype "passive"))
    )
    (net (code "47") (name "Net-(IC5A-QD)") (class "Default")
      (node (ref "IC5") (pin "3") (pinfunction "QD_3") (pintype "tri_state"))
      (node (ref "R12") (pin "1") (pinfunction "1_1") (pintype "passive"))
    )
    (net (code "48") (name "Net-(IC5A-QE)") (class "Default")
      (node (ref "IC5") (pin "4") (pinfunction "QE_4") (pintype "tri_state"))
      (node (ref "R13") (pin "1") (pinfunction "1_1") (pintype "passive"))
    )
    (net (code "49") (name "Net-(IC5A-QF)") (class "Default")
      (node (ref "IC5") (pin "5") (pinfunction "QF_5") (pintype "tri_state"))
      (node (ref "R14") (pin "1") (pinfunction "1_1") (pintype "passive"))
    )
    (net (code "50") (name "Net-(IC5A-QG)") (class "Default")
      (node (ref "IC5") (pin "6") (pinfunction "QG_6") (pintype "tri_state"))
      (node (ref "R15") (pin "1") (pinfunction "1_1") (pintype "passive"))
    )
    (net (code "51") (name "Net-(IC5A-QH)") (class "Default")
      (node (ref "IC5") (pin "7") (pinfunction "QH_7") (pintype "tri_state"))
      (node (ref "R16") (pin "1") (pinfunction "1_1") (pintype "passive"))
    )
    (net (code "52") (name "Net-(IC5A-QH*)") (class "Default")
      (node (ref "IC5") (pin "9") (pinfunction "QH*_9") (pintype "tri_state"))
      (node (ref "IC6") (pin "14") (pinfunction "SER_14") (pintype "input"))
    )
    (net (code "53") (name "Net-(IC6A-QA)") (class "Default")
      (node (ref "IC6") (pin "15") (pinfunction "QA_15") (pintype "tri_state"))
      (node (ref "R17") (pin "1") (pinfunction "1_1") (pintype "passive"))
    )
    (net (code "54") (name "Net-(IC6A-QB)") (class "Default")
      (node (ref "IC6") (pin "1") (pinfunction "QB_1") (pintype "tri_state"))
      (node (ref "R18") (pin "1") (pinfunction "1_1") (pintype "passive"))
    )
    (net (code "55") (name "Net-(IC6A-QC)") (class "Default")
      (node (ref "IC6") (pin "2") (pinfunction "QC_2") (pintype "tri_state"))
      (node (ref "R19") (pin "1") (pinfunction "1_1") (pintype "passive"))
    )
    (net (code "56") (name "Net-(IC6A-QD)") (class "Default")
      (node (ref "IC6") (pin "3") (pinfunction "QD_3") (pintype "tri_state"))
      (node (ref "R20") (pin "1") (pinfunction "1_1") (pintype "passive"))
    )
    (net (code "57") (name "Net-(IC6A-QE)") (class "Default")
      (node (ref "IC6") (pin "4") (pinfunction "QE_4") (pintype "tri_state"))
      (node (ref "R21") (pin "1") (pinfunction "1_1") (pintype "passive"))
    )
    (net (code "58") (name "Net-(IC6A-QF)") (class "Default")
      (node (ref "IC6") (pin "5") (pinfunction "QF_5") (pintype "tri_state"))
      (node (ref "R22") (pin "1") (pinfunction "1_1") (pintype "passive"))
    )
    (net (code "59") (name "Net-(IC6A-QG)") (class "Default")
      (node (ref "IC6") (pin "6") (pinfunction "QG_6") (pintype "tri_state"))
      (node (ref "R23") (pin "1") (pinfunction "1_1") (pintype "passive"))
    )
    (net (code "60") (name "Net-(IC6A-QH)") (class "Default")
      (node (ref "IC6") (pin "7") (pinfunction "QH_7") (pintype "tri_state"))
      (node (ref "R24") (pin "1") (pinfunction "1_1") (pintype "passive"))
    )
    (net (code "61") (name "Net-(LED1-PadA)") (class "Default")
      (node (ref "LED1") (pin "A") (pinfunction "A_A") (pintype "passive"))
      (node (ref "R1") (pin "2") (pinfunction "2_2") (pintype "passive"))
    )
    (net (code "62") (name "Net-(LED2-PadA)") (class "Default")
      (node (ref "LED2") (pin "A") (pinfunction "A_A") (pintype "passive"))
      (node (ref "R2") (pin "2") (pinfunction "2_2") (pintype "passive"))
    )
    (net (code "63") (name "Net-(LED3-PadA)") (class "Default")
      (node (ref "LED3") (pin "A") (pinfunction "A_A") (pintype "passive"))
      (node (ref "R3") (pin "2") (pinfunction "2_2") (pintype "passive"))
    )
    (net (code "64") (name "Net-(LED4-PadA)") (class "Default")
      (node (ref "LED4") (pin "A") (pinfunction "A_A") (pintype "passive"))
      (node (ref "R4") (pin "2") (pinfunction "2_2") (pintype "passive"))
    )
    (net (code "65") (name "Net-(LED5-PadA)") (class "Default")
      (node (ref "LED5") (pin "A") (pinfunction "A_A") (pintype "passive"))
      (node (ref "R5") (pin "2") (pinfunction "2_2") (pintype "passive"))
    )
    (net (code "66") (name "Net-(LED6-PadA)") (class "Default")
      (node (ref "LED6") (pin "A") (pinfunction "A_A") (pintype "passive"))
      (node (ref "R6") (pin "2") (pinfunction "2_2") (pintype "passive"))
    )
    (net (code "67") (name "Net-(LED7-PadA)") (class "Default")
      (node (ref "LED7") (pin "A") (pinfunction "A_A") (pintype "passive"))
      (node (ref "R7") (pin "2") (pinfunction "2_2") (pintype "passive"))
    )
    (net (code "68") (name "Net-(LED8-PadA)") (class "Default")
      (node (ref "LED8") (pin "A") (pinfunction "A_A") (pintype "passive"))
      (node (ref "R8") (pin "2") (pinfunction "2_2") (pintype "passive"))
    )
    (net (code "69") (name "Net-(LED9-PadA)") (class "Default")
      (node (ref "LED9") (pin "A") (pinfunction "A_A") (pintype "passive"))
      (node (ref "R9") (pin "2") (pinfunction "2_2") (pintype "passive"))
    )
    (net (code "70") (name "Net-(LED10-PadA)") (class "Default")
      (node (ref "LED10") (pin "A") (pinfunction "A_A") (pintype "passive"))
      (node (ref "R10") (pin "2") (pinfunction "2_2") (pintype "passive"))
    )
    (net (code "71") (name "Net-(LED11-PadA)") (class "Default")
      (node (ref "LED11") (pin "A") (pinfunction "A_A") (pintype "passive"))
      (node (ref "R11") (pin "2") (pinfunction "2_2") (pintype "passive"))
    )
    (net (code "72") (name "Net-(LED12-PadA)") (class "Default")
      (node (ref "LED12") (pin "A") (pinfunction "A_A") (pintype "passive"))
      (node (ref "R12") (pin "2") (pinfunction "2_2") (pintype "passive"))
    )
    (net (code "73") (name "Net-(LED13-PadA)") (class "Default")
      (node (ref "LED13") (pin "A") (pinfunction "A_A") (pintype "passive"))
      (node (ref "R13") (pin "2") (pinfunction "2_2") (pintype "passive"))
    )
    (net (code "74") (name "Net-(LED14-PadA)") (class "Default")
      (node (ref "LED14") (pin "A") (pinfunction "A_A") (pintype "passive"))
      (node (ref "R14") (pin "2") (pinfunction "2_2") (pintype "passive"))
    )
    (net (code "75") (name "Net-(LED15-PadA)") (class "Default")
      (node (ref "LED15") (pin "A") (pinfunction "A_A") (pintype "passive"))
      (node (ref "R15") (pin "2") (pinfunction "2_2") (pintype "passive"))
    )
    (net (code "76") (name "Net-(LED16-PadA)") (class "Default")
      (node (ref "LED16") (pin "A") (pinfunction "A_A") (pintype "passive"))
      (node (ref "R16") (pin "2") (pinfunction "2_2") (pintype "passive"))
    )
    (net (code "77") (name "Net-(LED17-PadA)") (class "Default")
      (node (ref "LED17") (pin "A") (pinfunction "A_A") (pintype "passive"))
      (node (ref "R17") (pin "2") (pinfunction "2_2") (pintype "passive"))
    )
    (net (code "78") (name "Net-(LED18-PadA)") (class "Default")
      (node (ref "LED18") (pin "A") (pinfunction "A_A") (pintype "passive"))
      (node (ref "R18") (pin "2") (pinfunction "2_2") (pintype "passive"))
    )
    (net (code "79") (name "Net-(LED19-PadA)") (class "Default")
      (node (ref "LED19") (pin "A") (pinfunction "A_A") (pintype "passive"))
      (node (ref "R19") (pin "2") (pinfunction "2_2") (pintype "passive"))
    )
    (net (code "80") (name "Net-(LED20-PadA)") (class "Default")
      (node (ref "LED20") (pin "A") (pinfunction "A_A") (pintype "passive"))
      (node (ref "R20") (pin "2") (pinfunction "2_2") (pintype "passive"))
    )
    (net (code "81") (name "Net-(LED21-PadA)") (class "Default")
      (node (ref "LED21") (pin "A") (pinfunction "A_A") (pintype "passive"))
      (node (ref "R21") (pin "2") (pinfunction "2_2") (pintype "passive"))
    )
    (net (code "82") (name "Net-(LED22-PadA)") (class "Default")
      (node (ref "LED22") (pin "A") (pinfunction "A_A") (pintype "passive"))
      (node (ref "R22") (pin "2") (pinfunction "2_2") (pintype "passive"))
    )
    (net (code "83") (name "Net-(LED23-PadA)") (class "Default")
      (node (ref "LED23") (pin "A") (pinfunction "A_A") (pintype "passive"))
      (node (ref "R23") (pin "2") (pinfunction "2_2") (pintype "passive"))
    )
    (net (code "84") (name "Net-(LED24-PadA)") (class "Default")
      (node (ref "LED24") (pin "A") (pinfunction "A_A") (pintype "passive"))
      (node (ref "R24") (pin "2") (pinfunction "2_2") (pintype "passive"))
    )
    (net (code "85") (name "unconnected-(IC1A-~{QH}-Pad7)") (class "Default")
      (node (ref "IC1") (pin "7") (pinfunction "~{QH}_7") (pintype "output"))
    )
    (net (code "86") (name "unconnected-(IC2A-~{QH}-Pad7)") (class "Default")
      (node (ref "IC2") (pin "7") (pinfunction "~{QH}_7") (pintype "output"))
    )
    (net (code "87") (name "unconnected-(IC3A-~{QH}-Pad7)") (class "Default")
      (node (ref "IC3") (pin "7") (pinfunction "~{QH}_7") (pintype "output"))
    )
    (net (code "88") (name "unconnected-(IC4A-G-Pad13)") (class "Default")
      (node (ref "IC4") (pin "13") (pinfunction "G_13") (pintype "input"))
    )
    (net (code "89") (name "unconnected-(IC4A-SCL-Pad10)") (class "Default")
      (node (ref "IC4") (pin "10") (pinfunction "SCL_10") (pintype "input"))
    )
    (net (code "90") (name "unconnected-(IC5A-G-Pad13)") (class "Default")
      (node (ref "IC5") (pin "13") (pinfunction "G_13") (pintype "input"))
    )
    (net (code "91") (name "unconnected-(IC5A-SCL-Pad10)") (class "Default")
      (node (ref "IC5") (pin "10") (pinfunction "SCL_10") (pintype "input"))
    )
    (net (code "92") (name "unconnected-(IC6A-G-Pad13)") (class "Default")
      (node (ref "IC6") (pin "13") (pinfunction "G_13") (pintype "input"))
    )
    (net (code "93") (name "unconnected-(IC6A-QH*-Pad9)") (class "Default")
      (node (ref "IC6") (pin "9") (pinfunction "QH*_9") (pintype "tri_state"))
    )
    (net (code "94") (name "unconnected-(IC6A-SCL-Pad10)") (class "Default")
      (node (ref "IC6") (pin "10") (pinfunction "SCL_10") (pintype "input"))
    )
    (net (code "95") (name "unconnected-(SHIFT-Pad1)") (class "Default")
      (node (ref "SHIFT") (pin "1") (pinfunction "1_1") (pintype "passive"))
    )
    (net (code "96") (name "unconnected-(SHIFT-Pad3)") (class "Default")
      (node (ref "SHIFT") (pin "3") (pinfunction "3_3") (pintype "passive"))
    )
    (net (code "97") (name "unconnected-(SHIFT-Pad6)") (class "Default")
      (node (ref "SHIFT") (pin "6") (pinfunction "6_6") (pintype "passive"))
    )
  )
)
